# Handle_Button.net
KiCad netlist of a schematic drawn in Altium Designer
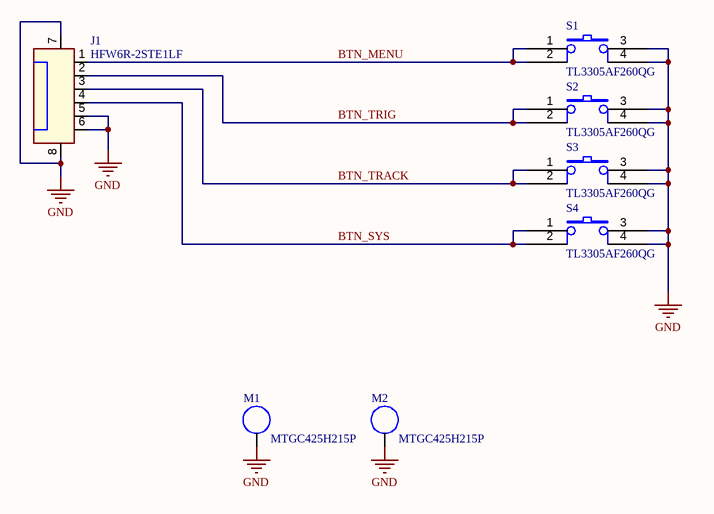
[diagram p0: Handle_Button.SchDoc]

(export (version "E")
  (design (tool "Eeschema 10.0.6"))
  (components
    (comp (ref "J1")
      (value "HFW6R-2STE1LF")
      (footprint "CON_FCI_HFW6R")
      (description "CONN FFC FPC TOP 6POS 1.00MM R/A")
      (fields (field (name "MFG") "Amphenol FCI"))
      (libsource (lib "SynapseLibrary") (part "HEADER 6 TABS"))
    )
    (comp (ref "M1")
      (value "MTGC425H215P")
      (footprint "MTGC425H215P")
      (description "MTG, 4.25mm PAD, 2.15mm Plated Hole")
      (libsource (lib "SynapseLibrary") (part "MTG"))
    )
    (comp (ref "M2")
      (value "MTGC425H215P")
      (footprint "MTGC425H215P")
      (description "MTG, 4.25mm PAD, 2.15mm Plated Hole")
      (libsource (lib "SynapseLibrary") (part "MTG"))
    )
    (comp (ref "S1")
      (value "TL3305AF260QG")
      (footprint "SW_TL3305_G")
      (description "SWITCH TACTILE SPST-NO 50MA 12V")
      (fields (field (name "PART NUMBER") "TL3301AF260QG") (field (name "MANUFACTURER") "E-Switch"))
      (libsource (lib "SynapseLibrary") (part "ESWITCH_TL3301AF"))
    )
    (comp (ref "S2")
      (value "TL3305AF260QG")
      (footprint "SW_TL3305_G")
      (description "SWITCH TACTILE SPST-NO 50MA 12V")
      (fields (field (name "PART NUMBER") "TL3301AF260QG") (field (name "MANUFACTURER") "E-Switch"))
      (libsource (lib "SynapseLibrary") (part "ESWITCH_TL3301AF"))
    )
    (comp (ref "S3")
      (value "TL3305AF260QG")
      (footprint "SW_TL3305_G")
      (description "SWITCH TACTILE SPST-NO 50MA 12V")
      (fields (field (name "PART NUMBER") "TL3301AF260QG") (field (name "MANUFACTURER") "E-Switch"))
      (libsource (lib "SynapseLibrary") (part "ESWITCH_TL3301AF"))
    )
    (comp (ref "S4")
      (value "TL3305AF260QG")
      (footprint "SW_TL3305_G")
      (description "SWITCH TACTILE SPST-NO 50MA 12V")
      (fields (field (name "PART NUMBER") "TL3301AF260QG") (field (name "MANUFACTURER") "E-Switch"))
      (libsource (lib "SynapseLibrary") (part "ESWITCH_TL3301AF"))
    )
  )
  (nets
    (net (code "1") (name "/BTN_MENU") (class "Default")
      (node (ref "J1") (pin "1") (pinfunction "1_1") (pintype "passive"))
      (node (ref "S1") (pin "1") (pinfunction "1_1") (pintype "passive"))
      (node (ref "S1") (pin "2") (pinfunction "2_2") (pintype "passive"))
    )
    (net (code "2") (name "/BTN_SYS") (class "Default")
      (node (ref "J1") (pin "4") (pinfunction "4_4") (pintype "passive"))
      (node (ref "S4") (pin "1") (pinfunction "1_1") (pintype "passive"))
      (node (ref "S4") (pin "2") (pinfunction "2_2") (pintype "passive"))
    )
    (net (code "3") (name "/BTN_TRACK") (class "Default")
      (node (ref "J1") (pin "3") (pinfunction "3_3") (pintype "passive"))
      (node (ref "S3") (pin "1") (pinfunction "1_1") (pintype "passive"))
      (node (ref "S3") (pin "2") (pinfunction "2_2") (pintype "passive"))
    )
    (net (code "4") (name "/BTN_TRIG") (class "Default")
      (node (ref "J1") (pin "2") (pinfunction "2_2") (pintype "passive"))
      (node (ref "S2") (pin "1") (pinfunction "1_1") (pintype "passive"))
      (node (ref "S2") (pin "2") (pinfunction "2_2") (pintype "passive"))
    )
    (net (code "5") (name "GND") (class "Default")
      (node (ref "J1") (pin "5") (pinfunction "5_5") (pintype "passive"))
      (node (ref "J1") (pin "6") (pinfunction "6_6") (pintype "passive"))
      (node (ref "J1") (pin "7") (pinfunction "7_7") (pintype "passive"))
      (node (ref "J1") (pin "8") (pinfunction "8_8") (pintype "passive"))
      (node (ref "M1") (pin "1") (pinfunction "1_1") (pintype "passive"))
      (node (ref "M2") (pin "1") (pinfunction "1_1") (pintype "passive"))
      (node (ref "S1") (pin "3") (pinfunction "3_3") (pintype "passive"))
      (node (ref "S1") (pin "4") (pinfunction "4_4") (pintype "passive"))
      (node (ref "S2") (pin "3") (pinfunction "3_3") (pintype "passive"))
      (node (ref "S2") (pin "4") (pinfunction "4_4") (pintype "passive"))
      (node (ref "S3") (pin "3") (pinfunction "3_3") (pintype "passive"))
      (node (ref "S3") (pin "4") (pinfunction "4_4") (pintype "passive"))
      (node (ref "S4") (pin "3") (pinfunction "3_3") (pintype "passive"))
      (node (ref "S4") (pin "4") (pinfunction "4_4") (pintype "passive"))
    )
  )
)
